# arduino_sheild.net
KiCad netlist of a schematic drawn in EAGLE
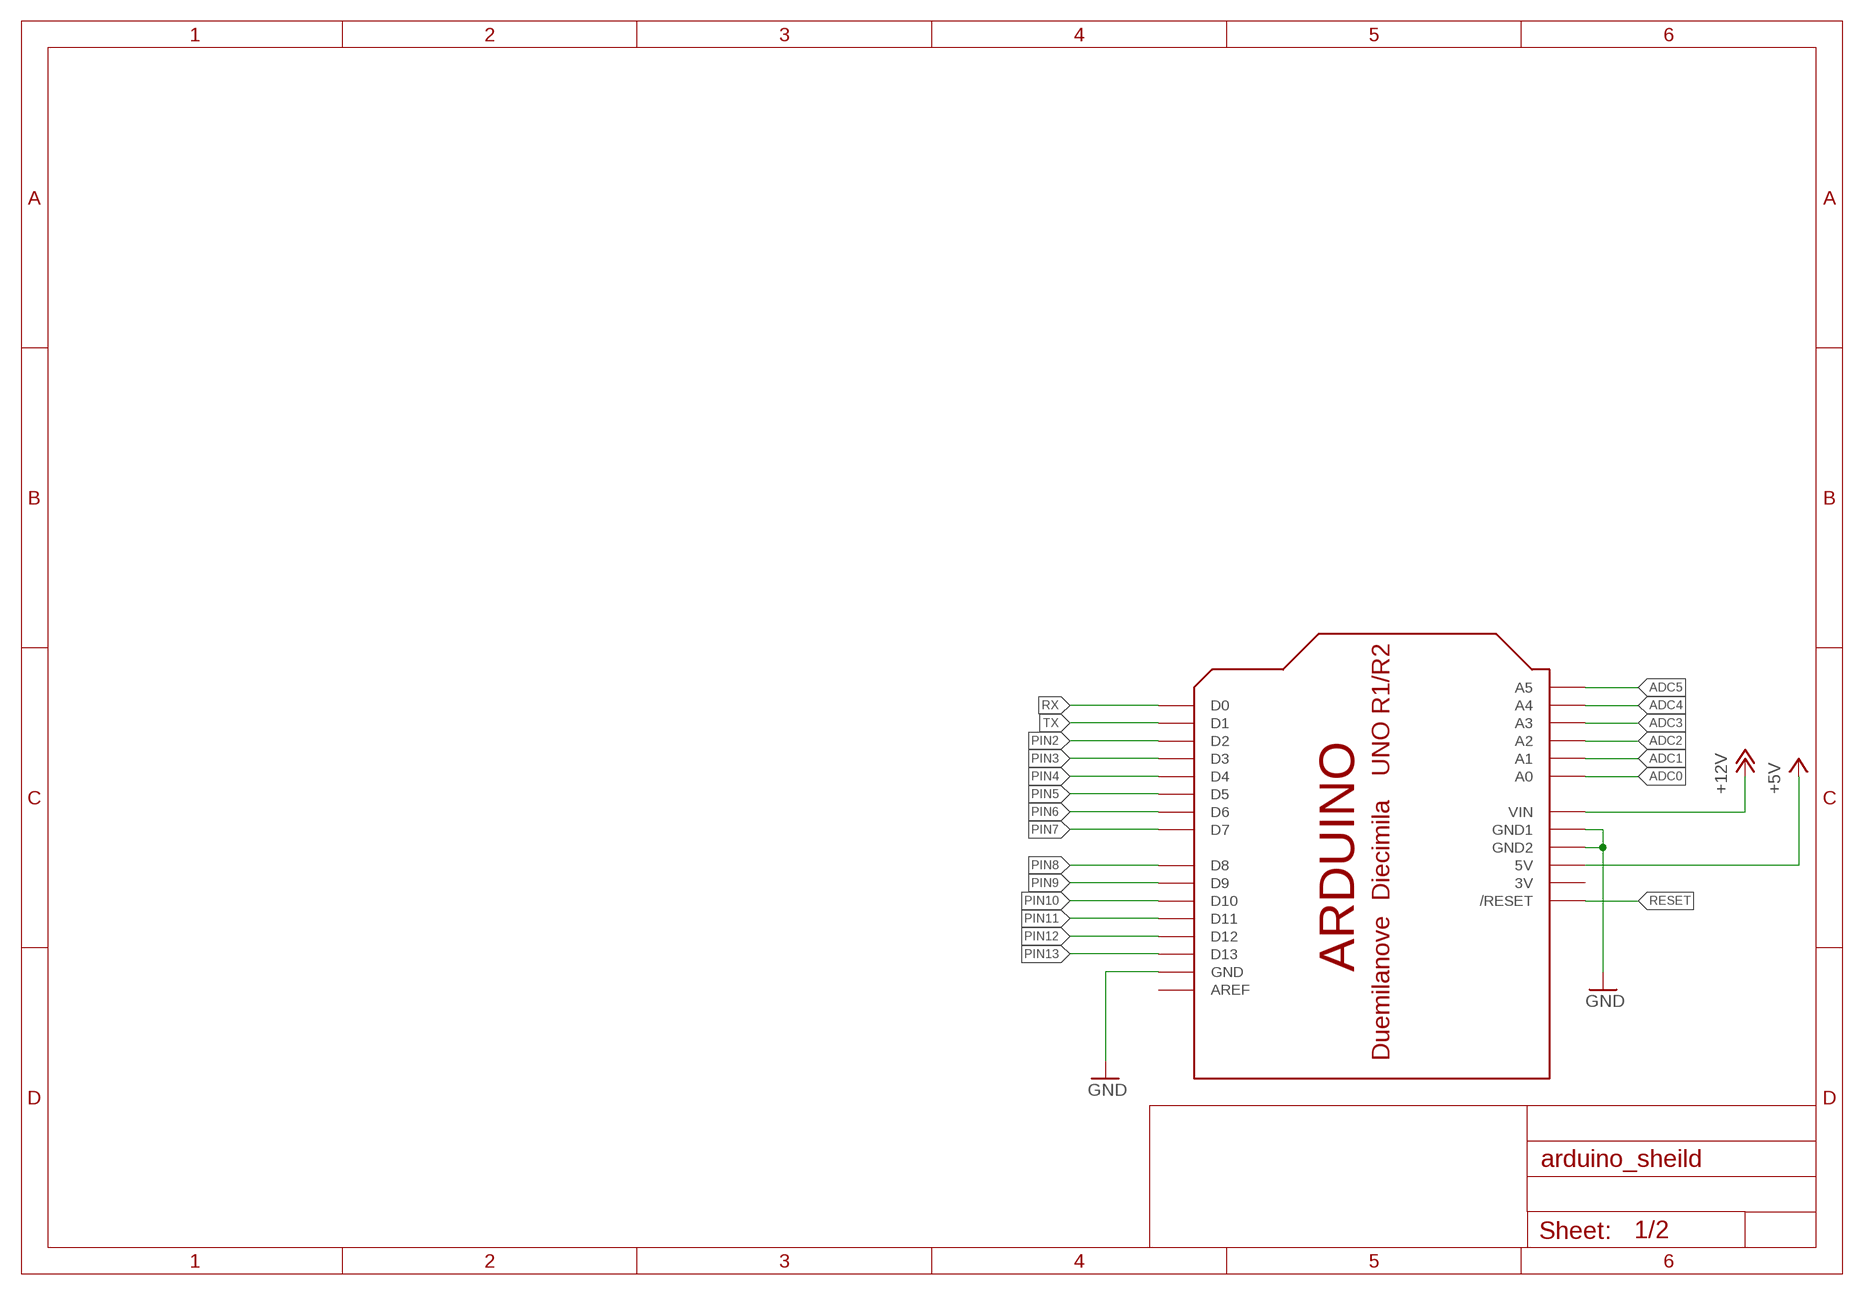
[diagram p0: schematic, sheet 1]
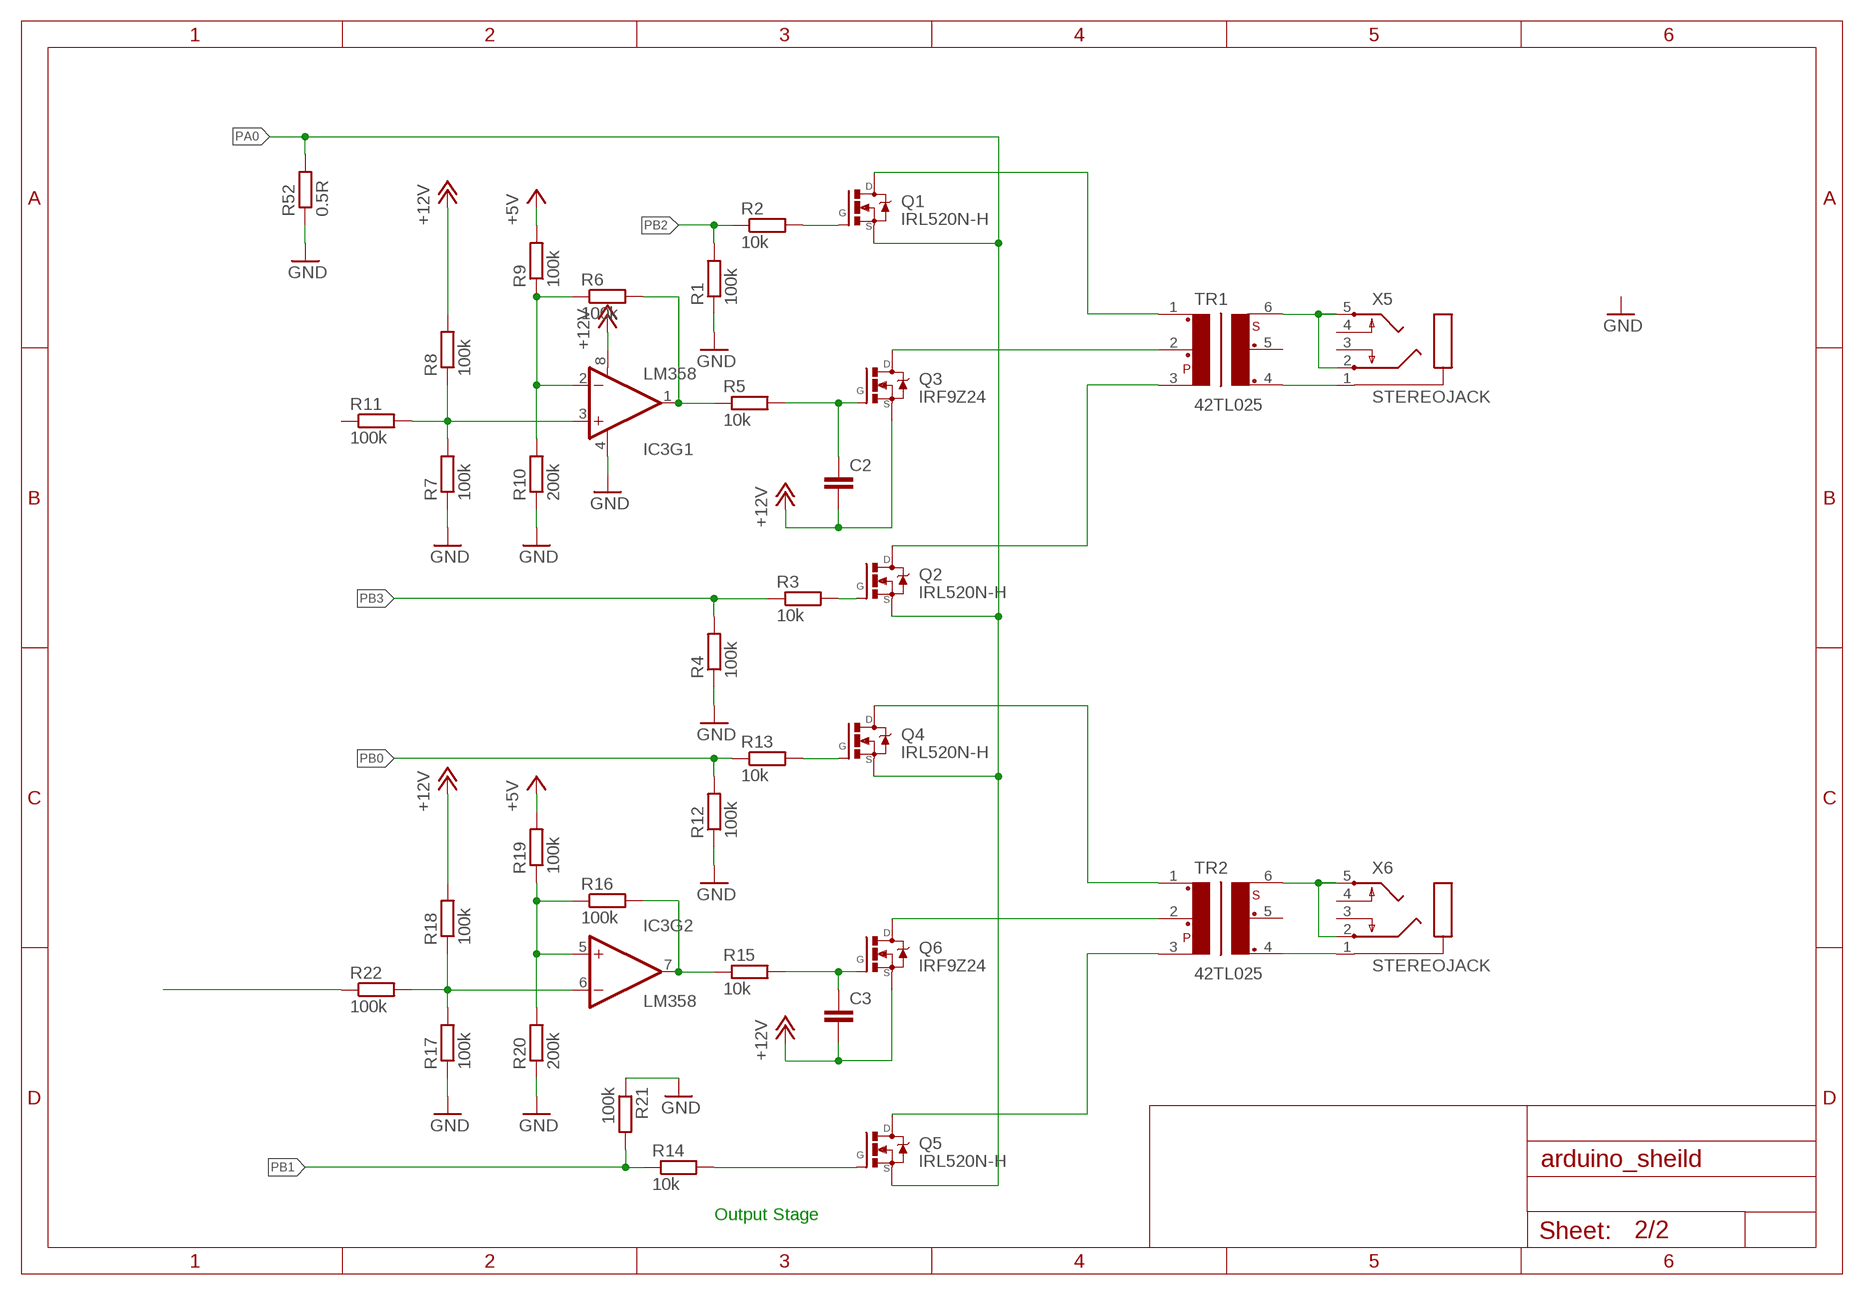
[diagram p1: schematic, sheet 2]

(export (version "E")
  (design (tool "Eeschema 10.0.6"))
  (components
    (comp (ref "U$3")
      (value "ARDUINOUNO")
      (footprint "eagle-import:ARDUINO")
      (libsource (lib "eagle-import") (part "ARDUINOUNO"))
    )
    (comp (ref "C2")
      (value "CAPPTH")
      (footprint "eagle-import:CAP-PTH-SMALL")
      (libsource (lib "eagle-import") (part "CAPPTH"))
    )
    (comp (ref "C3")
      (value "CAPPTH")
      (footprint "eagle-import:CAP-PTH-SMALL")
      (libsource (lib "eagle-import") (part "CAPPTH"))
    )
    (comp (ref "IC3")
      (value "LM358")
      (footprint "eagle-import:DIP08")
      (libsource (lib "eagle-import") (part "LM358"))
    )
    (comp (ref "Q1")
      (value "IRL520N-H")
      (footprint "eagle-import:TO220")
      (libsource (lib "eagle-import") (part "IRL530N-H"))
    )
    (comp (ref "Q2")
      (value "IRL520N-H")
      (footprint "eagle-import:TO220")
      (libsource (lib "eagle-import") (part "IRL530N-H"))
    )
    (comp (ref "Q3")
      (value "IRF9Z24")
      (footprint "eagle-import:TO220")
      (libsource (lib "eagle-import") (part "IRL530N-H"))
    )
    (comp (ref "Q4")
      (value "IRL520N-H")
      (footprint "eagle-import:TO220")
      (libsource (lib "eagle-import") (part "IRL530N-H"))
    )
    (comp (ref "Q5")
      (value "IRL520N-H")
      (footprint "eagle-import:TO220")
      (libsource (lib "eagle-import") (part "IRL530N-H"))
    )
    (comp (ref "Q6")
      (value "IRF9Z24")
      (footprint "eagle-import:TO220")
      (libsource (lib "eagle-import") (part "IRL530N-H"))
    )
    (comp (ref "R1")
      (value "100k")
      (footprint "eagle-import:0207_10")
      (libsource (lib "eagle-import") (part "R0207/10"))
    )
    (comp (ref "R2")
      (value "10k")
      (footprint "eagle-import:0207_10")
      (libsource (lib "eagle-import") (part "R0207/10"))
    )
    (comp (ref "R3")
      (value "10k")
      (footprint "eagle-import:0207_10")
      (libsource (lib "eagle-import") (part "R0207/10"))
    )
    (comp (ref "R4")
      (value "100k")
      (footprint "eagle-import:0207_10")
      (libsource (lib "eagle-import") (part "R0207/10"))
    )
    (comp (ref "R5")
      (value "10k")
      (footprint "eagle-import:0207_10")
      (libsource (lib "eagle-import") (part "R0207/10"))
    )
    (comp (ref "R6")
      (value "100k")
      (footprint "eagle-import:0207_10")
      (libsource (lib "eagle-import") (part "R0207/10"))
    )
    (comp (ref "R7")
      (value "100k")
      (footprint "eagle-import:0207_10")
      (libsource (lib "eagle-import") (part "R0207/10"))
    )
    (comp (ref "R8")
      (value "100k")
      (footprint "eagle-import:0207_10")
      (libsource (lib "eagle-import") (part "R0207/10"))
    )
    (comp (ref "R9")
      (value "100k")
      (footprint "eagle-import:0207_10")
      (libsource (lib "eagle-import") (part "R0207/10"))
    )
    (comp (ref "R10")
      (value "200k")
      (footprint "eagle-import:0207_10")
      (libsource (lib "eagle-import") (part "R0207/10"))
    )
    (comp (ref "R11")
      (value "100k")
      (footprint "eagle-import:0207_10")
      (libsource (lib "eagle-import") (part "R0207/10"))
    )
    (comp (ref "R12")
      (value "100k")
      (footprint "eagle-import:0207_10")
      (libsource (lib "eagle-import") (part "R0207/10"))
    )
    (comp (ref "R13")
      (value "10k")
      (footprint "eagle-import:0207_10")
      (libsource (lib "eagle-import") (part "R0207/10"))
    )
    (comp (ref "R14")
      (value "10k")
      (footprint "eagle-import:0207_10")
      (libsource (lib "eagle-import") (part "R0207/10"))
    )
    (comp (ref "R15")
      (value "10k")
      (footprint "eagle-import:0207_10")
      (libsource (lib "eagle-import") (part "R0207/10"))
    )
    (comp (ref "R16")
      (value "100k")
      (footprint "eagle-import:0207_10")
      (libsource (lib "eagle-import") (part "R0207/10"))
    )
    (comp (ref "R17")
      (value "100k")
      (footprint "eagle-import:0207_10")
      (libsource (lib "eagle-import") (part "R0207/10"))
    )
    (comp (ref "R18")
      (value "100k")
      (footprint "eagle-import:0207_10")
      (libsource (lib "eagle-import") (part "R0207/10"))
    )
    (comp (ref "R19")
      (value "100k")
      (footprint "eagle-import:0207_10")
      (libsource (lib "eagle-import") (part "R0207/10"))
    )
    (comp (ref "R20")
      (value "200k")
      (footprint "eagle-import:0207_10")
      (libsource (lib "eagle-import") (part "R0207/10"))
    )
    (comp (ref "R21")
      (value "100k")
      (footprint "eagle-import:0207_10")
      (libsource (lib "eagle-import") (part "R0207/10"))
    )
    (comp (ref "R22")
      (value "100k")
      (footprint "eagle-import:0207_10")
      (libsource (lib "eagle-import") (part "R0207/10"))
    )
    (comp (ref "R52")
      (value "0.5R")
      (footprint "eagle-import:0207_10")
      (libsource (lib "eagle-import") (part "R0207/10"))
    )
    (comp (ref "TR1")
      (value "42TL025")
      (footprint "eagle-import:42TL")
      (libsource (lib "eagle-import") (part "42T?L025"))
    )
    (comp (ref "TR2")
      (value "42TL025")
      (footprint "eagle-import:42TL")
      (libsource (lib "eagle-import") (part "42T?L025"))
    )
    (comp (ref "X5")
      (value "STEREOJACK")
      (footprint "eagle-import:STX3100")
      (libsource (lib "eagle-import") (part "STEREOJACK"))
    )
    (comp (ref "X6")
      (value "STEREOJACK")
      (footprint "eagle-import:STX3100")
      (libsource (lib "eagle-import") (part "STEREOJACK"))
    )
  )
  (nets
    (net (code "1") (name "+5V") (class "Default")
      (node (ref "R19") (pin "2") (pinfunction "2_2") (pintype "passive"))
      (node (ref "R9") (pin "2") (pinfunction "2_2") (pintype "passive"))
      (node (ref "U$3") (pin "5V") (pinfunction "5V_5V") (pintype "power_in"))
    )
    (net (code "2") (name "+12V") (class "Default")
      (node (ref "C2") (pin "2") (pinfunction "2_2") (pintype "passive"))
      (node (ref "C3") (pin "2") (pinfunction "2_2") (pintype "passive"))
      (node (ref "IC3") (pin "8") (pinfunction "V+_8") (pintype "power_in"))
      (node (ref "Q3") (pin "3") (pinfunction "S_3") (pintype "passive"))
      (node (ref "Q6") (pin "3") (pinfunction "S_3") (pintype "passive"))
      (node (ref "R18") (pin "2") (pinfunction "2_2") (pintype "passive"))
      (node (ref "R8") (pin "2") (pinfunction "2_2") (pintype "passive"))
      (node (ref "U$3") (pin "VIN") (pinfunction "VIN_VIN") (pintype "power_in"))
    )
    (net (code "3") (name "3V") (class "Default")
      (node (ref "U$3") (pin "3V") (pinfunction "3V_3V") (pintype "power_in"))
    )
    (net (code "4") (name "ADC0") (class "Default")
      (node (ref "U$3") (pin "A0") (pinfunction "A0_A0") (pintype "bidirectional"))
    )
    (net (code "5") (name "ADC1") (class "Default")
      (node (ref "U$3") (pin "A1") (pinfunction "A1_A1") (pintype "bidirectional"))
    )
    (net (code "6") (name "ADC2") (class "Default")
      (node (ref "U$3") (pin "A2") (pinfunction "A2_A2") (pintype "bidirectional"))
    )
    (net (code "7") (name "ADC3") (class "Default")
      (node (ref "U$3") (pin "A3") (pinfunction "A3_A3") (pintype "bidirectional"))
    )
    (net (code "8") (name "ADC4") (class "Default")
      (node (ref "U$3") (pin "A4") (pinfunction "A4_A4") (pintype "bidirectional"))
    )
    (net (code "9") (name "ADC5") (class "Default")
      (node (ref "U$3") (pin "A5") (pinfunction "A5_A5") (pintype "bidirectional"))
    )
    (net (code "10") (name "GND") (class "Default")
      (node (ref "IC3") (pin "4") (pinfunction "V-_4") (pintype "power_in"))
      (node (ref "R1") (pin "1") (pinfunction "1_1") (pintype "passive"))
      (node (ref "R10") (pin "1") (pinfunction "1_1") (pintype "passive"))
      (node (ref "R12") (pin "1") (pinfunction "1_1") (pintype "passive"))
      (node (ref "R17") (pin "1") (pinfunction "1_1") (pintype "passive"))
      (node (ref "R20") (pin "1") (pinfunction "1_1") (pintype "passive"))
      (node (ref "R21") (pin "1") (pinfunction "1_1") (pintype "passive"))
      (node (ref "R4") (pin "1") (pinfunction "1_1") (pintype "passive"))
      (node (ref "R52") (pin "1") (pinfunction "1_1") (pintype "passive"))
      (node (ref "R7") (pin "1") (pinfunction "1_1") (pintype "passive"))
      (node (ref "U$3") (pin "GND") (pinfunction "GND_GND") (pintype "power_in"))
      (node (ref "U$3") (pin "GND1") (pinfunction "GND1_GND1") (pintype "power_in"))
      (node (ref "U$3") (pin "GND2") (pinfunction "GND2_GND2") (pintype "power_in"))
    )
    (net (code "11") (name "Net-(IC3A-+IN)") (class "Default")
      (node (ref "IC3") (pin "3") (pinfunction "+IN_3") (pintype "input"))
      (node (ref "R11") (pin "2") (pinfunction "2_2") (pintype "passive"))
      (node (ref "R7") (pin "2") (pinfunction "2_2") (pintype "passive"))
      (node (ref "R8") (pin "1") (pinfunction "1_1") (pintype "passive"))
    )
    (net (code "12") (name "Net-(IC3A--IN)") (class "Default")
      (node (ref "IC3") (pin "2") (pinfunction "-IN_2") (pintype "input"))
      (node (ref "R10") (pin "2") (pinfunction "2_2") (pintype "passive"))
      (node (ref "R6") (pin "1") (pinfunction "1_1") (pintype "passive"))
      (node (ref "R9") (pin "1") (pinfunction "1_1") (pintype "passive"))
    )
    (net (code "13") (name "Net-(IC3A-OUT)") (class "Default")
      (node (ref "IC3") (pin "1") (pinfunction "OUT_1") (pintype "output"))
      (node (ref "R5") (pin "1") (pinfunction "1_1") (pintype "passive"))
      (node (ref "R6") (pin "2") (pinfunction "2_2") (pintype "passive"))
    )
    (net (code "14") (name "Net-(IC3B-+IN)") (class "Default")
      (node (ref "IC3") (pin "5") (pinfunction "+IN_5") (pintype "input"))
      (node (ref "R16") (pin "1") (pinfunction "1_1") (pintype "passive"))
      (node (ref "R19") (pin "1") (pinfunction "1_1") (pintype "passive"))
      (node (ref "R20") (pin "2") (pinfunction "2_2") (pintype "passive"))
    )
    (net (code "15") (name "Net-(IC3B--IN)") (class "Default")
      (node (ref "IC3") (pin "6") (pinfunction "-IN_6") (pintype "input"))
      (node (ref "R17") (pin "2") (pinfunction "2_2") (pintype "passive"))
      (node (ref "R18") (pin "1") (pinfunction "1_1") (pintype "passive"))
      (node (ref "R22") (pin "2") (pinfunction "2_2") (pintype "passive"))
    )
    (net (code "16") (name "Net-(IC3B-OUT)") (class "Default")
      (node (ref "IC3") (pin "7") (pinfunction "OUT_7") (pintype "output"))
      (node (ref "R15") (pin "1") (pinfunction "1_1") (pintype "passive"))
      (node (ref "R16") (pin "2") (pinfunction "2_2") (pintype "passive"))
    )
    (net (code "17") (name "Net-(Q1-D)") (class "Default")
      (node (ref "Q1") (pin "2") (pinfunction "D_2") (pintype "passive"))
      (node (ref "TR1") (pin "1") (pinfunction "1_1") (pintype "passive"))
    )
    (net (code "18") (name "Net-(Q1-G)") (class "Default")
      (node (ref "Q1") (pin "1") (pinfunction "G_1") (pintype "passive"))
      (node (ref "R2") (pin "2") (pinfunction "2_2") (pintype "passive"))
    )
    (net (code "19") (name "Net-(Q2-D)") (class "Default")
      (node (ref "Q2") (pin "2") (pinfunction "D_2") (pintype "passive"))
      (node (ref "TR1") (pin "3") (pinfunction "3_3") (pintype "passive"))
    )
    (net (code "20") (name "Net-(Q2-G)") (class "Default")
      (node (ref "Q2") (pin "1") (pinfunction "G_1") (pintype "passive"))
      (node (ref "R3") (pin "2") (pinfunction "2_2") (pintype "passive"))
    )
    (net (code "21") (name "Net-(Q3-D)") (class "Default")
      (node (ref "Q3") (pin "2") (pinfunction "D_2") (pintype "passive"))
      (node (ref "TR1") (pin "2") (pinfunction "2_2") (pintype "passive"))
    )
    (net (code "22") (name "Net-(Q3-G)") (class "Default")
      (node (ref "C2") (pin "1") (pinfunction "1_1") (pintype "passive"))
      (node (ref "Q3") (pin "1") (pinfunction "G_1") (pintype "passive"))
      (node (ref "R5") (pin "2") (pinfunction "2_2") (pintype "passive"))
    )
    (net (code "23") (name "Net-(Q4-D)") (class "Default")
      (node (ref "Q4") (pin "2") (pinfunction "D_2") (pintype "passive"))
      (node (ref "TR2") (pin "1") (pinfunction "1_1") (pintype "passive"))
    )
    (net (code "24") (name "Net-(Q4-G)") (class "Default")
      (node (ref "Q4") (pin "1") (pinfunction "G_1") (pintype "passive"))
      (node (ref "R13") (pin "2") (pinfunction "2_2") (pintype "passive"))
    )
    (net (code "25") (name "Net-(Q5-D)") (class "Default")
      (node (ref "Q5") (pin "2") (pinfunction "D_2") (pintype "passive"))
      (node (ref "TR2") (pin "3") (pinfunction "3_3") (pintype "passive"))
    )
    (net (code "26") (name "Net-(Q5-G)") (class "Default")
      (node (ref "Q5") (pin "1") (pinfunction "G_1") (pintype "passive"))
      (node (ref "R14") (pin "2") (pinfunction "2_2") (pintype "passive"))
    )
    (net (code "27") (name "Net-(Q6-D)") (class "Default")
      (node (ref "Q6") (pin "2") (pinfunction "D_2") (pintype "passive"))
      (node (ref "TR2") (pin "2") (pinfunction "2_2") (pintype "passive"))
    )
    (net (code "28") (name "Net-(Q6-G)") (class "Default")
      (node (ref "C3") (pin "1") (pinfunction "1_1") (pintype "passive"))
      (node (ref "Q6") (pin "1") (pinfunction "G_1") (pintype "passive"))
      (node (ref "R15") (pin "2") (pinfunction "2_2") (pintype "passive"))
    )
    (net (code "29") (name "Net-(TR1-Pad4)") (class "Default")
      (node (ref "TR1") (pin "4") (pinfunction "4_4") (pintype "passive"))
      (node (ref "X5") (pin "1") (pinfunction "1_1") (pintype "passive"))
    )
    (net (code "30") (name "Net-(TR1-Pad6)") (class "Default")
      (node (ref "TR1") (pin "6") (pinfunction "6_6") (pintype "passive"))
      (node (ref "X5") (pin "2") (pinfunction "2_2") (pintype "passive"))
      (node (ref "X5") (pin "5") (pinfunction "5_5") (pintype "passive"))
    )
    (net (code "31") (name "Net-(TR2-Pad4)") (class "Default")
      (node (ref "TR2") (pin "4") (pinfunction "4_4") (pintype "passive"))
      (node (ref "X6") (pin "1") (pinfunction "1_1") (pintype "passive"))
    )
    (net (code "32") (name "Net-(TR2-Pad6)") (class "Default")
      (node (ref "TR2") (pin "6") (pinfunction "6_6") (pintype "passive"))
      (node (ref "X6") (pin "2") (pinfunction "2_2") (pintype "passive"))
      (node (ref "X6") (pin "5") (pinfunction "5_5") (pintype "passive"))
    )
    (net (code "33") (name "PA0") (class "Default")
      (node (ref "Q1") (pin "3") (pinfunction "S_3") (pintype "passive"))
      (node (ref "Q2") (pin "3") (pinfunction "S_3") (pintype "passive"))
      (node (ref "Q4") (pin "3") (pinfunction "S_3") (pintype "passive"))
      (node (ref "Q5") (pin "3") (pinfunction "S_3") (pintype "passive"))
      (node (ref "R52") (pin "2") (pinfunction "2_2") (pintype "passive"))
    )
    (net (code "34") (name "PB0") (class "Default")
      (node (ref "R12") (pin "2") (pinfunction "2_2") (pintype "passive"))
      (node (ref "R13") (pin "1") (pinfunction "1_1") (pintype "passive"))
    )
    (net (code "35") (name "PB1") (class "Default")
      (node (ref "R14") (pin "1") (pinfunction "1_1") (pintype "passive"))
      (node (ref "R21") (pin "2") (pinfunction "2_2") (pintype "passive"))
    )
    (net (code "36") (name "PB2") (class "Default")
      (node (ref "R1") (pin "2") (pinfunction "2_2") (pintype "passive"))
      (node (ref "R2") (pin "1") (pinfunction "1_1") (pintype "passive"))
    )
    (net (code "37") (name "PB3") (class "Default")
      (node (ref "R3") (pin "1") (pinfunction "1_1") (pintype "passive"))
      (node (ref "R4") (pin "2") (pinfunction "2_2") (pintype "passive"))
    )
    (net (code "38") (name "PIN2") (class "Default")
      (node (ref "U$3") (pin "D2") (pinfunction "D2_D2") (pintype "bidirectional"))
    )
    (net (code "39") (name "PIN3") (class "Default")
      (node (ref "U$3") (pin "D3") (pinfunction "D3_D3") (pintype "bidirectional"))
    )
    (net (code "40") (name "PIN4") (class "Default")
      (node (ref "U$3") (pin "D4") (pinfunction "D4_D4") (pintype "bidirectional"))
    )
    (net (code "41") (name "PIN5") (class "Default")
      (node (ref "U$3") (pin "D5") (pinfunction "D5_D5") (pintype "bidirectional"))
    )
    (net (code "42") (name "PIN6") (class "Default")
      (node (ref "U$3") (pin "D6") (pinfunction "D6_D6") (pintype "bidirectional"))
    )
    (net (code "43") (name "PIN7") (class "Default")
      (node (ref "U$3") (pin "D7") (pinfunction "D7_D7") (pintype "bidirectional"))
    )
    (net (code "44") (name "PIN8") (class "Default")
      (node (ref "U$3") (pin "D8") (pinfunction "D8_D8") (pintype "bidirectional"))
    )
    (net (code "45") (name "PIN9") (class "Default")
      (node (ref "U$3") (pin "D9") (pinfunction "D9_D9") (pintype "bidirectional"))
    )
    (net (code "46") (name "PIN10") (class "Default")
      (node (ref "U$3") (pin "D10") (pinfunction "D10_D10") (pintype "bidirectional"))
    )
    (net (code "47") (name "PIN11") (class "Default")
      (node (ref "U$3") (pin "D11") (pinfunction "D11_D11") (pintype "bidirectional"))
    )
    (net (code "48") (name "PIN12") (class "Default")
      (node (ref "U$3") (pin "D12") (pinfunction "D12_D12") (pintype "bidirectional"))
    )
    (net (code "49") (name "PIN13") (class "Default")
      (node (ref "U$3") (pin "D13") (pinfunction "D13_D13") (pintype "bidirectional"))
    )
    (net (code "50") (name "RESET") (class "Default")
      (node (ref "U$3") (pin "RESET") (pinfunction "/RESET_RESET") (pintype "bidirectional"))
    )
    (net (code "51") (name "RX") (class "Default")
      (node (ref "U$3") (pin "D0") (pinfunction "D0_D0") (pintype "bidirectional"))
    )
    (net (code "52") (name "TX") (class "Default")
      (node (ref "U$3") (pin "D1") (pinfunction "D1_D1") (pintype "bidirectional"))
    )
    (net (code "53") (name "unconnected-(R11-Pad1)") (class "Default")
      (node (ref "R11") (pin "1") (pinfunction "1_1") (pintype "passive"))
    )
    (net (code "54") (name "unconnected-(R22-Pad1)") (class "Default")
      (node (ref "R22") (pin "1") (pinfunction "1_1") (pintype "passive"))
    )
    (net (code "55") (name "unconnected-(TR1-Pad5)") (class "Default")
      (node (ref "TR1") (pin "5") (pinfunction "5_5") (pintype "passive"))
    )
    (net (code "56") (name "unconnected-(TR2-Pad5)") (class "Default")
      (node (ref "TR2") (pin "5") (pinfunction "5_5") (pintype "passive"))
    )
    (net (code "57") (name "unconnected-(U$3-PadAREF)") (class "Default")
      (node (ref "U$3") (pin "AREF") (pinfunction "AREF_AREF") (pintype "bidirectional"))
    )
    (net (code "58") (name "unconnected-(X5-Pad3)") (class "Default")
      (node (ref "X5") (pin "3") (pinfunction "3_3") (pintype "passive"))
    )
    (net (code "59") (name "unconnected-(X5-Pad4)") (class "Default")
      (node (ref "X5") (pin "4") (pinfunction "4_4") (pintype "passive"))
    )
    (net (code "60") (name "unconnected-(X6-Pad3)") (class "Default")
      (node (ref "X6") (pin "3") (pinfunction "3_3") (pintype "passive"))
    )
    (net (code "61") (name "unconnected-(X6-Pad4)") (class "Default")
      (node (ref "X6") (pin "4") (pinfunction "4_4") (pintype "passive"))
    )
  )
)
